# realParking.net
KiCad netlist of a schematic drawn in EAGLE
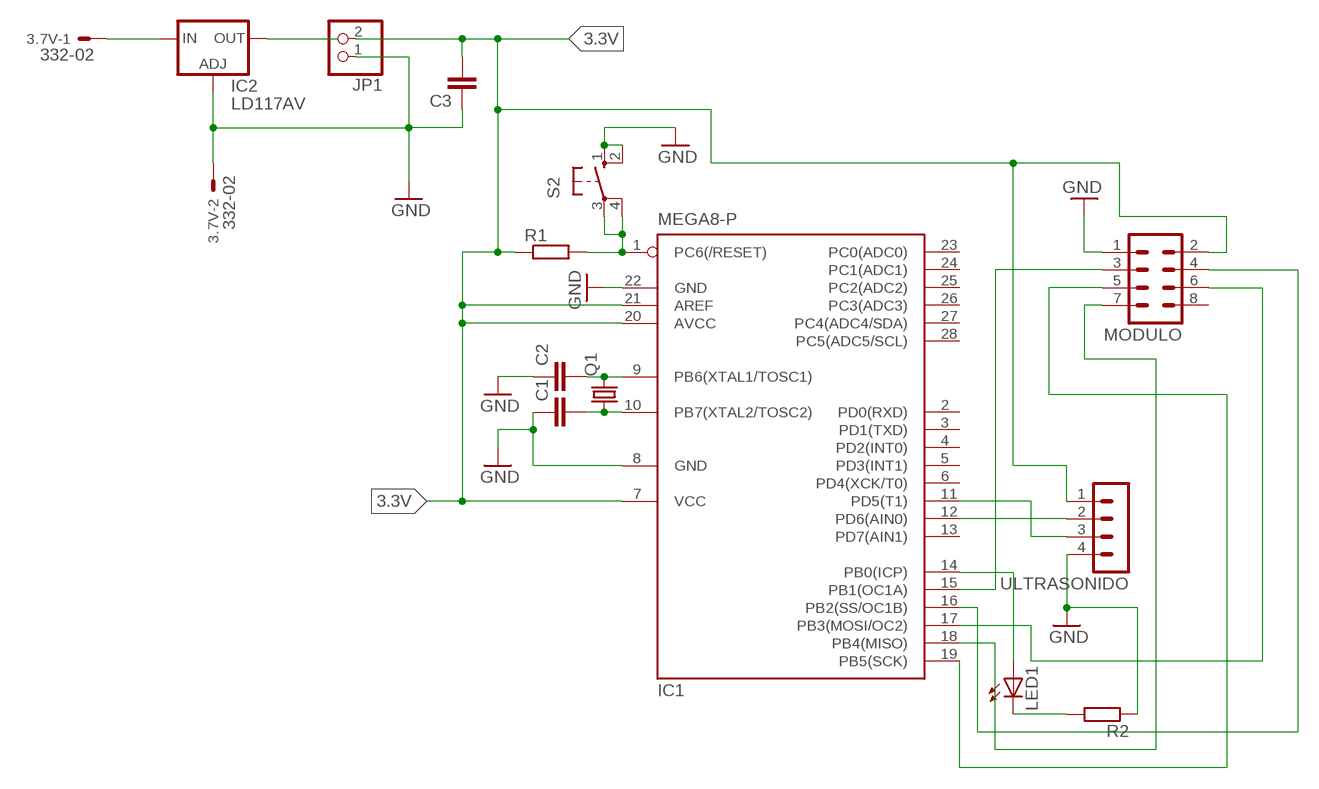
[diagram p0: schematic, sheet 1]

(export (version "E")
  (design (tool "Eeschema 10.0.6"))
  (components
    (comp (ref "3.7V")
      (value "332-02")
      (footprint "eagle-import:332-02")
      (libsource (lib "eagle-import") (part "332-02"))
    )
    (comp (ref "C1")
      (value "C2,5-3")
      (footprint "eagle-import:C2.5-3")
      (libsource (lib "eagle-import") (part "C2,5-3"))
    )
    (comp (ref "C2")
      (value "C2,5-3")
      (footprint "eagle-import:C2.5-3")
      (libsource (lib "eagle-import") (part "C2,5-3"))
    )
    (comp (ref "C3")
      (value "C2,5-3")
      (footprint "eagle-import:C2.5-3")
      (libsource (lib "eagle-import") (part "C2,5-3"))
    )
    (comp (ref "IC1")
      (value "MEGA8-P")
      (footprint "eagle-import:DIL28-3")
      (libsource (lib "eagle-import") (part "MEGA8-P"))
    )
    (comp (ref "IC2")
      (value "LD117AV")
      (footprint "eagle-import:TO220L1")
      (libsource (lib "eagle-import") (part "LD117A?V"))
    )
    (comp (ref "JP1")
      (value "PINHD-1X2")
      (footprint "eagle-import:1X02")
      (libsource (lib "eagle-import") (part "PINHD-1X2"))
    )
    (comp (ref "LED1")
      (value "LED5MM")
      (footprint "eagle-import:LED5MM")
      (libsource (lib "eagle-import") (part "LED5MM"))
    )
    (comp (ref "MODULO")
      (value "MA04-2")
      (footprint "eagle-import:MA04-2")
      (libsource (lib "eagle-import") (part "MA04-2"))
    )
    (comp (ref "Q1")
      (value "CRYSTALTC26V")
      (footprint "eagle-import:TC26V")
      (libsource (lib "eagle-import") (part "CRYSTALTC26V"))
    )
    (comp (ref "R1")
      (value "R-EU_0204/5")
      (footprint "eagle-import:0204_5")
      (libsource (lib "eagle-import") (part "R-EU_0204/5"))
    )
    (comp (ref "R2")
      (value "R-EU_0204/5")
      (footprint "eagle-import:0204_5")
      (libsource (lib "eagle-import") (part "R-EU_0204/5"))
    )
    (comp (ref "S2")
      (value "10-XX")
      (footprint "eagle-import:B3F-10XX")
      (fields (field (name "MPN") "B3F-1000"))
      (libsource (lib "eagle-import") (part "10-XX"))
    )
    (comp (ref "ULTRASONIDO")
      (value "MA04-1")
      (footprint "eagle-import:MA04-1")
      (libsource (lib "eagle-import") (part "MA04-1"))
    )
  )
  (nets
    (net (code "1") (name "3.3V") (class "Default")
      (node (ref "C3") (pin "2") (pinfunction "2_2") (pintype "passive"))
      (node (ref "IC1") (pin "20") (pinfunction "AVCC_20") (pintype "power_in"))
      (node (ref "IC1") (pin "21") (pinfunction "AREF_21") (pintype "passive"))
      (node (ref "IC1") (pin "7") (pinfunction "VCC_7") (pintype "power_in"))
      (node (ref "JP1") (pin "2") (pinfunction "2_2") (pintype "passive"))
      (node (ref "MODULO") (pin "2") (pinfunction "2_2") (pintype "passive"))
      (node (ref "R1") (pin "1") (pinfunction "1_1") (pintype "passive"))
      (node (ref "ULTRASONIDO") (pin "1") (pinfunction "1_1") (pintype "passive"))
    )
    (net (code "2") (name "GND") (class "Default")
      (node (ref "3.7V") (pin "2") (pinfunction "S_2") (pintype "passive"))
      (node (ref "C1") (pin "1") (pinfunction "1_1") (pintype "passive"))
      (node (ref "C2") (pin "1") (pinfunction "1_1") (pintype "passive"))
      (node (ref "C3") (pin "1") (pinfunction "1_1") (pintype "passive"))
      (node (ref "IC1") (pin "22") (pinfunction "GND_22") (pintype "power_in"))
      (node (ref "IC1") (pin "8") (pinfunction "GND_8") (pintype "power_in"))
      (node (ref "IC2") (pin "1") (pinfunction "ADJ_1") (pintype "input"))
      (node (ref "JP1") (pin "1") (pinfunction "1_1") (pintype "passive"))
      (node (ref "MODULO") (pin "1") (pinfunction "1_1") (pintype "passive"))
      (node (ref "R2") (pin "1") (pinfunction "1_1") (pintype "passive"))
      (node (ref "S2") (pin "1") (pinfunction "S_1") (pintype "passive"))
      (node (ref "S2") (pin "2") (pinfunction "S1_2") (pintype "passive"))
      (node (ref "ULTRASONIDO") (pin "4") (pinfunction "4_4") (pintype "passive"))
    )
    (net (code "3") (name "Net-(3.7VA-S)") (class "Default")
      (node (ref "3.7V") (pin "1") (pinfunction "S_1") (pintype "passive"))
      (node (ref "IC2") (pin "3") (pinfunction "IN_3") (pintype "input"))
    )
    (net (code "4") (name "Net-(IC1-PB0(ICP))") (class "Default")
      (node (ref "IC1") (pin "14") (pinfunction "PB0(ICP)_14") (pintype "bidirectional"))
      (node (ref "LED1") (pin "A") (pinfunction "A_A") (pintype "passive"))
    )
    (net (code "5") (name "Net-(IC1-PB1(OC1A))") (class "Default")
      (node (ref "IC1") (pin "15") (pinfunction "PB1(OC1A)_15") (pintype "bidirectional"))
      (node (ref "MODULO") (pin "3") (pinfunction "3_3") (pintype "passive"))
    )
    (net (code "6") (name "Net-(IC1-PB2(SS{slash}OC1B))") (class "Default")
      (node (ref "IC1") (pin "16") (pinfunction "PB2(SS/OC1B)_16") (pintype "bidirectional"))
      (node (ref "MODULO") (pin "4") (pinfunction "4_4") (pintype "passive"))
    )
    (net (code "7") (name "Net-(IC1-PB3(MOSI{slash}OC2))") (class "Default")
      (node (ref "IC1") (pin "17") (pinfunction "PB3(MOSI/OC2)_17") (pintype "bidirectional"))
      (node (ref "MODULO") (pin "6") (pinfunction "6_6") (pintype "passive"))
    )
    (net (code "8") (name "Net-(IC1-PB4(MISO))") (class "Default")
      (node (ref "IC1") (pin "18") (pinfunction "PB4(MISO)_18") (pintype "bidirectional"))
      (node (ref "MODULO") (pin "7") (pinfunction "7_7") (pintype "passive"))
    )
    (net (code "9") (name "Net-(IC1-PB5(SCK))") (class "Default")
      (node (ref "IC1") (pin "19") (pinfunction "PB5(SCK)_19") (pintype "bidirectional"))
      (node (ref "MODULO") (pin "5") (pinfunction "5_5") (pintype "passive"))
    )
    (net (code "10") (name "Net-(IC1-PB6(XTAL1{slash}TOSC1))") (class "Default")
      (node (ref "C2") (pin "2") (pinfunction "2_2") (pintype "passive"))
      (node (ref "IC1") (pin "9") (pinfunction "PB6(XTAL1/TOSC1)_9") (pintype "bidirectional"))
      (node (ref "Q1") (pin "2") (pinfunction "2_2") (pintype "passive"))
    )
    (net (code "11") (name "Net-(IC1-PB7(XTAL2{slash}TOSC2))") (class "Default")
      (node (ref "C1") (pin "2") (pinfunction "2_2") (pintype "passive"))
      (node (ref "IC1") (pin "10") (pinfunction "PB7(XTAL2/TOSC2)_10") (pintype "bidirectional"))
      (node (ref "Q1") (pin "1") (pinfunction "1_1") (pintype "passive"))
    )
    (net (code "12") (name "Net-(IC1-PC6({slash}RESET))") (class "Default")
      (node (ref "IC1") (pin "1") (pinfunction "PC6(/RESET)_1") (pintype "bidirectional"))
      (node (ref "R1") (pin "2") (pinfunction "2_2") (pintype "passive"))
      (node (ref "S2") (pin "3") (pinfunction "P_3") (pintype "passive"))
      (node (ref "S2") (pin "4") (pinfunction "P1_4") (pintype "passive"))
    )
    (net (code "13") (name "Net-(IC1-PD5(T1))") (class "Default")
      (node (ref "IC1") (pin "11") (pinfunction "PD5(T1)_11") (pintype "bidirectional"))
      (node (ref "ULTRASONIDO") (pin "3") (pinfunction "3_3") (pintype "passive"))
    )
    (net (code "14") (name "Net-(IC1-PD6(AIN0))") (class "Default")
      (node (ref "IC1") (pin "12") (pinfunction "PD6(AIN0)_12") (pintype "bidirectional"))
      (node (ref "ULTRASONIDO") (pin "2") (pinfunction "2_2") (pintype "passive"))
    )
    (net (code "15") (name "Net-(LED1-C)") (class "Default")
      (node (ref "LED1") (pin "K") (pinfunction "C_K") (pintype "passive"))
      (node (ref "R2") (pin "2") (pinfunction "2_2") (pintype "passive"))
    )
    (net (code "16") (name "unconnected-(IC1-PC0(ADC0)-Pad23)") (class "Default")
      (node (ref "IC1") (pin "23") (pinfunction "PC0(ADC0)_23") (pintype "bidirectional"))
    )
    (net (code "17") (name "unconnected-(IC1-PC1(ADC1)-Pad24)") (class "Default")
      (node (ref "IC1") (pin "24") (pinfunction "PC1(ADC1)_24") (pintype "bidirectional"))
    )
    (net (code "18") (name "unconnected-(IC1-PC2(ADC2)-Pad25)") (class "Default")
      (node (ref "IC1") (pin "25") (pinfunction "PC2(ADC2)_25") (pintype "bidirectional"))
    )
    (net (code "19") (name "unconnected-(IC1-PC3(ADC3)-Pad26)") (class "Default")
      (node (ref "IC1") (pin "26") (pinfunction "PC3(ADC3)_26") (pintype "bidirectional"))
    )
    (net (code "20") (name "unconnected-(IC1-PC4(ADC4{slash}SDA)-Pad27)") (class "Default")
      (node (ref "IC1") (pin "27") (pinfunction "PC4(ADC4/SDA)_27") (pintype "bidirectional"))
    )
    (net (code "21") (name "unconnected-(IC1-PC5(ADC5{slash}SCL)-Pad28)") (class "Default")
      (node (ref "IC1") (pin "28") (pinfunction "PC5(ADC5/SCL)_28") (pintype "bidirectional"))
    )
    (net (code "22") (name "unconnected-(IC1-PD0(RXD)-Pad2)") (class "Default")
      (node (ref "IC1") (pin "2") (pinfunction "PD0(RXD)_2") (pintype "bidirectional"))
    )
    (net (code "23") (name "unconnected-(IC1-PD1(TXD)-Pad3)") (class "Default")
      (node (ref "IC1") (pin "3") (pinfunction "PD1(TXD)_3") (pintype "bidirectional"))
    )
    (net (code "24") (name "unconnected-(IC1-PD2(INT0)-Pad4)") (class "Default")
      (node (ref "IC1") (pin "4") (pinfunction "PD2(INT0)_4") (pintype "bidirectional"))
    )
    (net (code "25") (name "unconnected-(IC1-PD3(INT1)-Pad5)") (class "Default")
      (node (ref "IC1") (pin "5") (pinfunction "PD3(INT1)_5") (pintype "bidirectional"))
    )
    (net (code "26") (name "unconnected-(IC1-PD4(XCK{slash}T0)-Pad6)") (class "Default")
      (node (ref "IC1") (pin "6") (pinfunction "PD4(XCK/T0)_6") (pintype "bidirectional"))
    )
    (net (code "27") (name "unconnected-(IC1-PD7(AIN1)-Pad13)") (class "Default")
      (node (ref "IC1") (pin "13") (pinfunction "PD7(AIN1)_13") (pintype "bidirectional"))
    )
    (net (code "28") (name "unconnected-(IC2-OUT-Pad2)") (class "Default")
      (node (ref "IC2") (pin "2") (pinfunction "OUT_2") (pintype "passive"))
    )
    (net (code "29") (name "unconnected-(MODULO-Pad8)") (class "Default")
      (node (ref "MODULO") (pin "8") (pinfunction "8_8") (pintype "passive"))
    )
  )
)
